# rapport.net
KiCad netlist of a schematic drawn in EAGLE
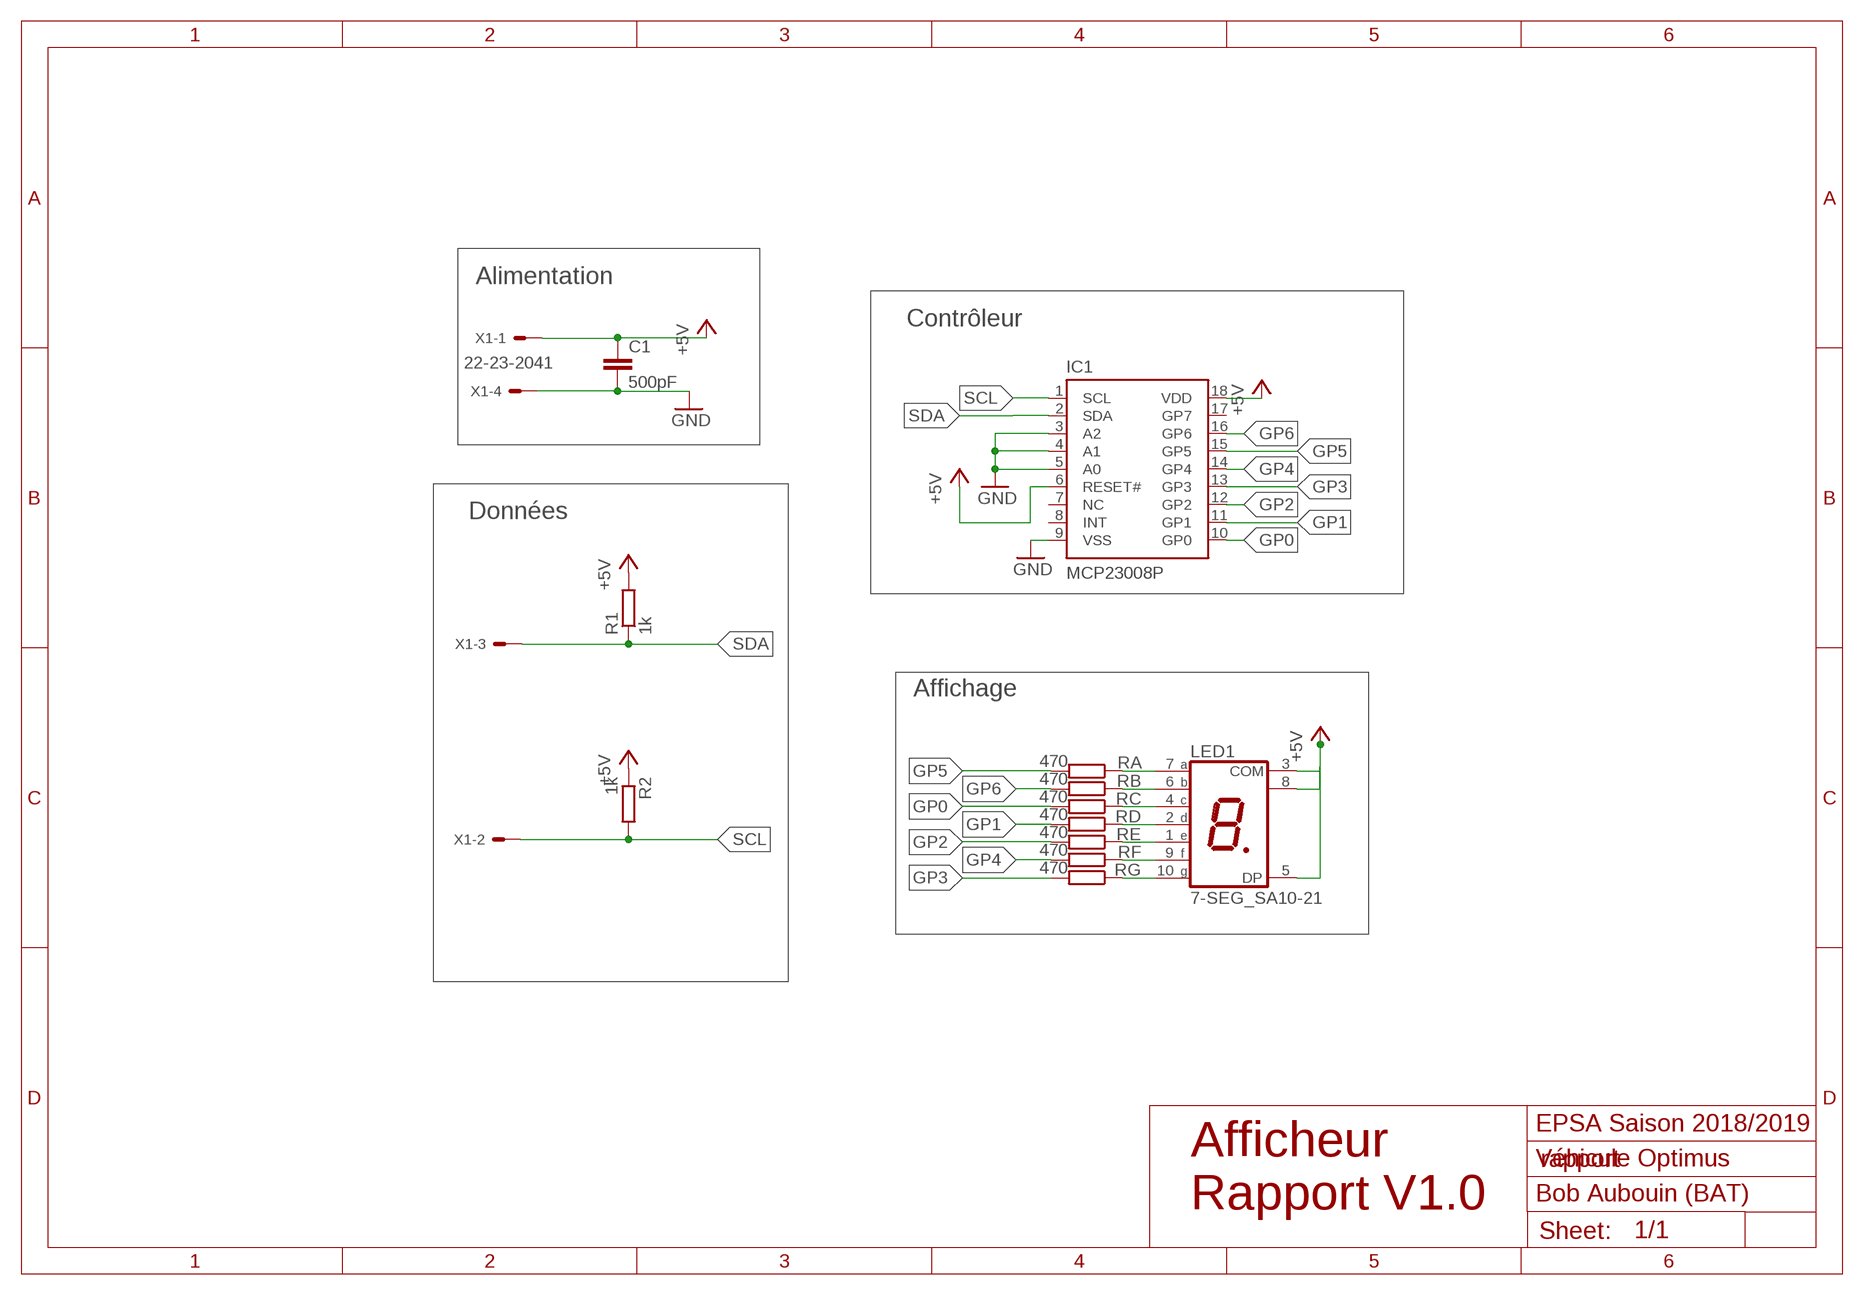
[diagram p0: schematic, sheet 1]

(export (version "E")
  (design (tool "Eeschema 10.0.6"))
  (components
    (comp (ref "C1")
      (value "500pF")
      (footprint "eagle-import:C025-025X050")
      (libsource (lib "eagle-import") (part "C-EU025-025X050"))
    )
    (comp (ref "IC1")
      (value "MCP23008P")
      (footprint "eagle-import:DIL18")
      (libsource (lib "eagle-import") (part "MCP23008P"))
    )
    (comp (ref "LED1")
      (value "7-SEG_SA10-21")
      (footprint "eagle-import:SA10-21")
      (libsource (lib "eagle-import") (part "7-SEG_SA10-21"))
    )
    (comp (ref "R1")
      (value "1k")
      (footprint "eagle-import:0204_7")
      (libsource (lib "eagle-import") (part "R-EU_0204/7"))
    )
    (comp (ref "R2")
      (value "1k")
      (footprint "eagle-import:0204_7")
      (libsource (lib "eagle-import") (part "R-EU_0204/7"))
    )
    (comp (ref "RA")
      (value "470")
      (footprint "eagle-import:0204_7")
      (libsource (lib "eagle-import") (part "R-EU_0204/7"))
    )
    (comp (ref "RB")
      (value "470")
      (footprint "eagle-import:0204_7")
      (libsource (lib "eagle-import") (part "R-EU_0204/7"))
    )
    (comp (ref "RC")
      (value "470")
      (footprint "eagle-import:0204_7")
      (libsource (lib "eagle-import") (part "R-EU_0204/7"))
    )
    (comp (ref "RD")
      (value "470")
      (footprint "eagle-import:0204_7")
      (libsource (lib "eagle-import") (part "R-EU_0204/7"))
    )
    (comp (ref "RE")
      (value "470")
      (footprint "eagle-import:0204_7")
      (libsource (lib "eagle-import") (part "R-EU_0204/7"))
    )
    (comp (ref "RF")
      (value "470")
      (footprint "eagle-import:0204_7")
      (libsource (lib "eagle-import") (part "R-EU_0204/7"))
    )
    (comp (ref "RG")
      (value "470")
      (footprint "eagle-import:0204_7")
      (libsource (lib "eagle-import") (part "R-EU_0204/7"))
    )
    (comp (ref "X1")
      (value "22-23-2041")
      (footprint "eagle-import:22-23-2041")
      (fields (field (name "MF") "MOLEX"))
      (libsource (lib "eagle-import") (part "22-23-2041"))
    )
  )
  (nets
    (net (code "1") (name "+5V") (class "Default")
      (node (ref "C1") (pin "1") (pinfunction "1_1") (pintype "passive"))
      (node (ref "IC1") (pin "18") (pinfunction "VDD_18") (pintype "power_in"))
      (node (ref "IC1") (pin "6") (pinfunction "RESET#_6") (pintype "input"))
      (node (ref "LED1") (pin "3") (pinfunction "COM_3") (pintype "passive"))
      (node (ref "LED1") (pin "5") (pinfunction "DP_5") (pintype "passive"))
      (node (ref "LED1") (pin "8") (pinfunction "COM_8") (pintype "passive"))
      (node (ref "R1") (pin "2") (pinfunction "2_2") (pintype "passive"))
      (node (ref "R2") (pin "1") (pinfunction "1_1") (pintype "passive"))
      (node (ref "X1") (pin "1") (pinfunction "S_1") (pintype "passive"))
    )
    (net (code "2") (name "GND") (class "Default")
      (node (ref "C1") (pin "2") (pinfunction "2_2") (pintype "passive"))
      (node (ref "IC1") (pin "3") (pinfunction "A2_3") (pintype "input"))
      (node (ref "IC1") (pin "4") (pinfunction "A1_4") (pintype "input"))
      (node (ref "IC1") (pin "5") (pinfunction "A0_5") (pintype "input"))
      (node (ref "IC1") (pin "9") (pinfunction "VSS_9") (pintype "power_in"))
      (node (ref "X1") (pin "4") (pinfunction "S_4") (pintype "passive"))
    )
    (net (code "3") (name "GP0") (class "Default")
      (node (ref "IC1") (pin "10") (pinfunction "GP0_10") (pintype "bidirectional"))
      (node (ref "RC") (pin "2") (pinfunction "2_2") (pintype "passive"))
    )
    (net (code "4") (name "GP1") (class "Default")
      (node (ref "IC1") (pin "11") (pinfunction "GP1_11") (pintype "bidirectional"))
      (node (ref "RD") (pin "2") (pinfunction "2_2") (pintype "passive"))
    )
    (net (code "5") (name "GP2") (class "Default")
      (node (ref "IC1") (pin "12") (pinfunction "GP2_12") (pintype "bidirectional"))
      (node (ref "RE") (pin "2") (pinfunction "2_2") (pintype "passive"))
    )
    (net (code "6") (name "GP3") (class "Default")
      (node (ref "IC1") (pin "13") (pinfunction "GP3_13") (pintype "bidirectional"))
      (node (ref "RG") (pin "2") (pinfunction "2_2") (pintype "passive"))
    )
    (net (code "7") (name "GP4") (class "Default")
      (node (ref "IC1") (pin "14") (pinfunction "GP4_14") (pintype "bidirectional"))
      (node (ref "RF") (pin "2") (pinfunction "2_2") (pintype "passive"))
    )
    (net (code "8") (name "GP5") (class "Default")
      (node (ref "IC1") (pin "15") (pinfunction "GP5_15") (pintype "bidirectional"))
      (node (ref "RA") (pin "2") (pinfunction "2_2") (pintype "passive"))
    )
    (net (code "9") (name "GP6") (class "Default")
      (node (ref "IC1") (pin "16") (pinfunction "GP6_16") (pintype "bidirectional"))
      (node (ref "RB") (pin "2") (pinfunction "2_2") (pintype "passive"))
    )
    (net (code "10") (name "Net-(LED1-A)") (class "Default")
      (node (ref "LED1") (pin "7") (pinfunction "A_7") (pintype "passive"))
      (node (ref "RA") (pin "1") (pinfunction "1_1") (pintype "passive"))
    )
    (net (code "11") (name "Net-(LED1-B)") (class "Default")
      (node (ref "LED1") (pin "6") (pinfunction "B_6") (pintype "passive"))
      (node (ref "RB") (pin "1") (pinfunction "1_1") (pintype "passive"))
    )
    (net (code "12") (name "Net-(LED1-C)") (class "Default")
      (node (ref "LED1") (pin "4") (pinfunction "C_4") (pintype "passive"))
      (node (ref "RC") (pin "1") (pinfunction "1_1") (pintype "passive"))
    )
    (net (code "13") (name "Net-(LED1-D)") (class "Default")
      (node (ref "LED1") (pin "2") (pinfunction "D_2") (pintype "passive"))
      (node (ref "RD") (pin "1") (pinfunction "1_1") (pintype "passive"))
    )
    (net (code "14") (name "Net-(LED1-E)") (class "Default")
      (node (ref "LED1") (pin "1") (pinfunction "E_1") (pintype "passive"))
      (node (ref "RE") (pin "1") (pinfunction "1_1") (pintype "passive"))
    )
    (net (code "15") (name "Net-(LED1-F)") (class "Default")
      (node (ref "LED1") (pin "9") (pinfunction "F_9") (pintype "passive"))
      (node (ref "RF") (pin "1") (pinfunction "1_1") (pintype "passive"))
    )
    (net (code "16") (name "Net-(LED1-G)") (class "Default")
      (node (ref "LED1") (pin "10") (pinfunction "G_10") (pintype "passive"))
      (node (ref "RG") (pin "1") (pinfunction "1_1") (pintype "passive"))
    )
    (net (code "17") (name "SCL") (class "Default")
      (node (ref "IC1") (pin "1") (pinfunction "SCL_1") (pintype "input"))
      (node (ref "R2") (pin "2") (pinfunction "2_2") (pintype "passive"))
      (node (ref "X1") (pin "2") (pinfunction "S_2") (pintype "passive"))
    )
    (net (code "18") (name "SDA") (class "Default")
      (node (ref "IC1") (pin "2") (pinfunction "SDA_2") (pintype "bidirectional"))
      (node (ref "R1") (pin "1") (pinfunction "1_1") (pintype "passive"))
      (node (ref "X1") (pin "3") (pinfunction "S_3") (pintype "passive"))
    )
    (net (code "19") (name "unconnected-(IC1-GP7-Pad17)") (class "Default")
      (node (ref "IC1") (pin "17") (pinfunction "GP7_17") (pintype "bidirectional"))
    )
    (net (code "20") (name "unconnected-(IC1-INT-Pad8)") (class "Default")
      (node (ref "IC1") (pin "8") (pinfunction "INT_8") (pintype "output"))
    )
    (net (code "21") (name "unconnected-(IC1-NC-Pad7)") (class "Default")
      (node (ref "IC1") (pin "7") (pinfunction "NC_7") (pintype "no_connect"))
    )
  )
)
